# kk_sem_ultrahang_hw.net
KiCad netlist of a schematic drawn in Altium Designer
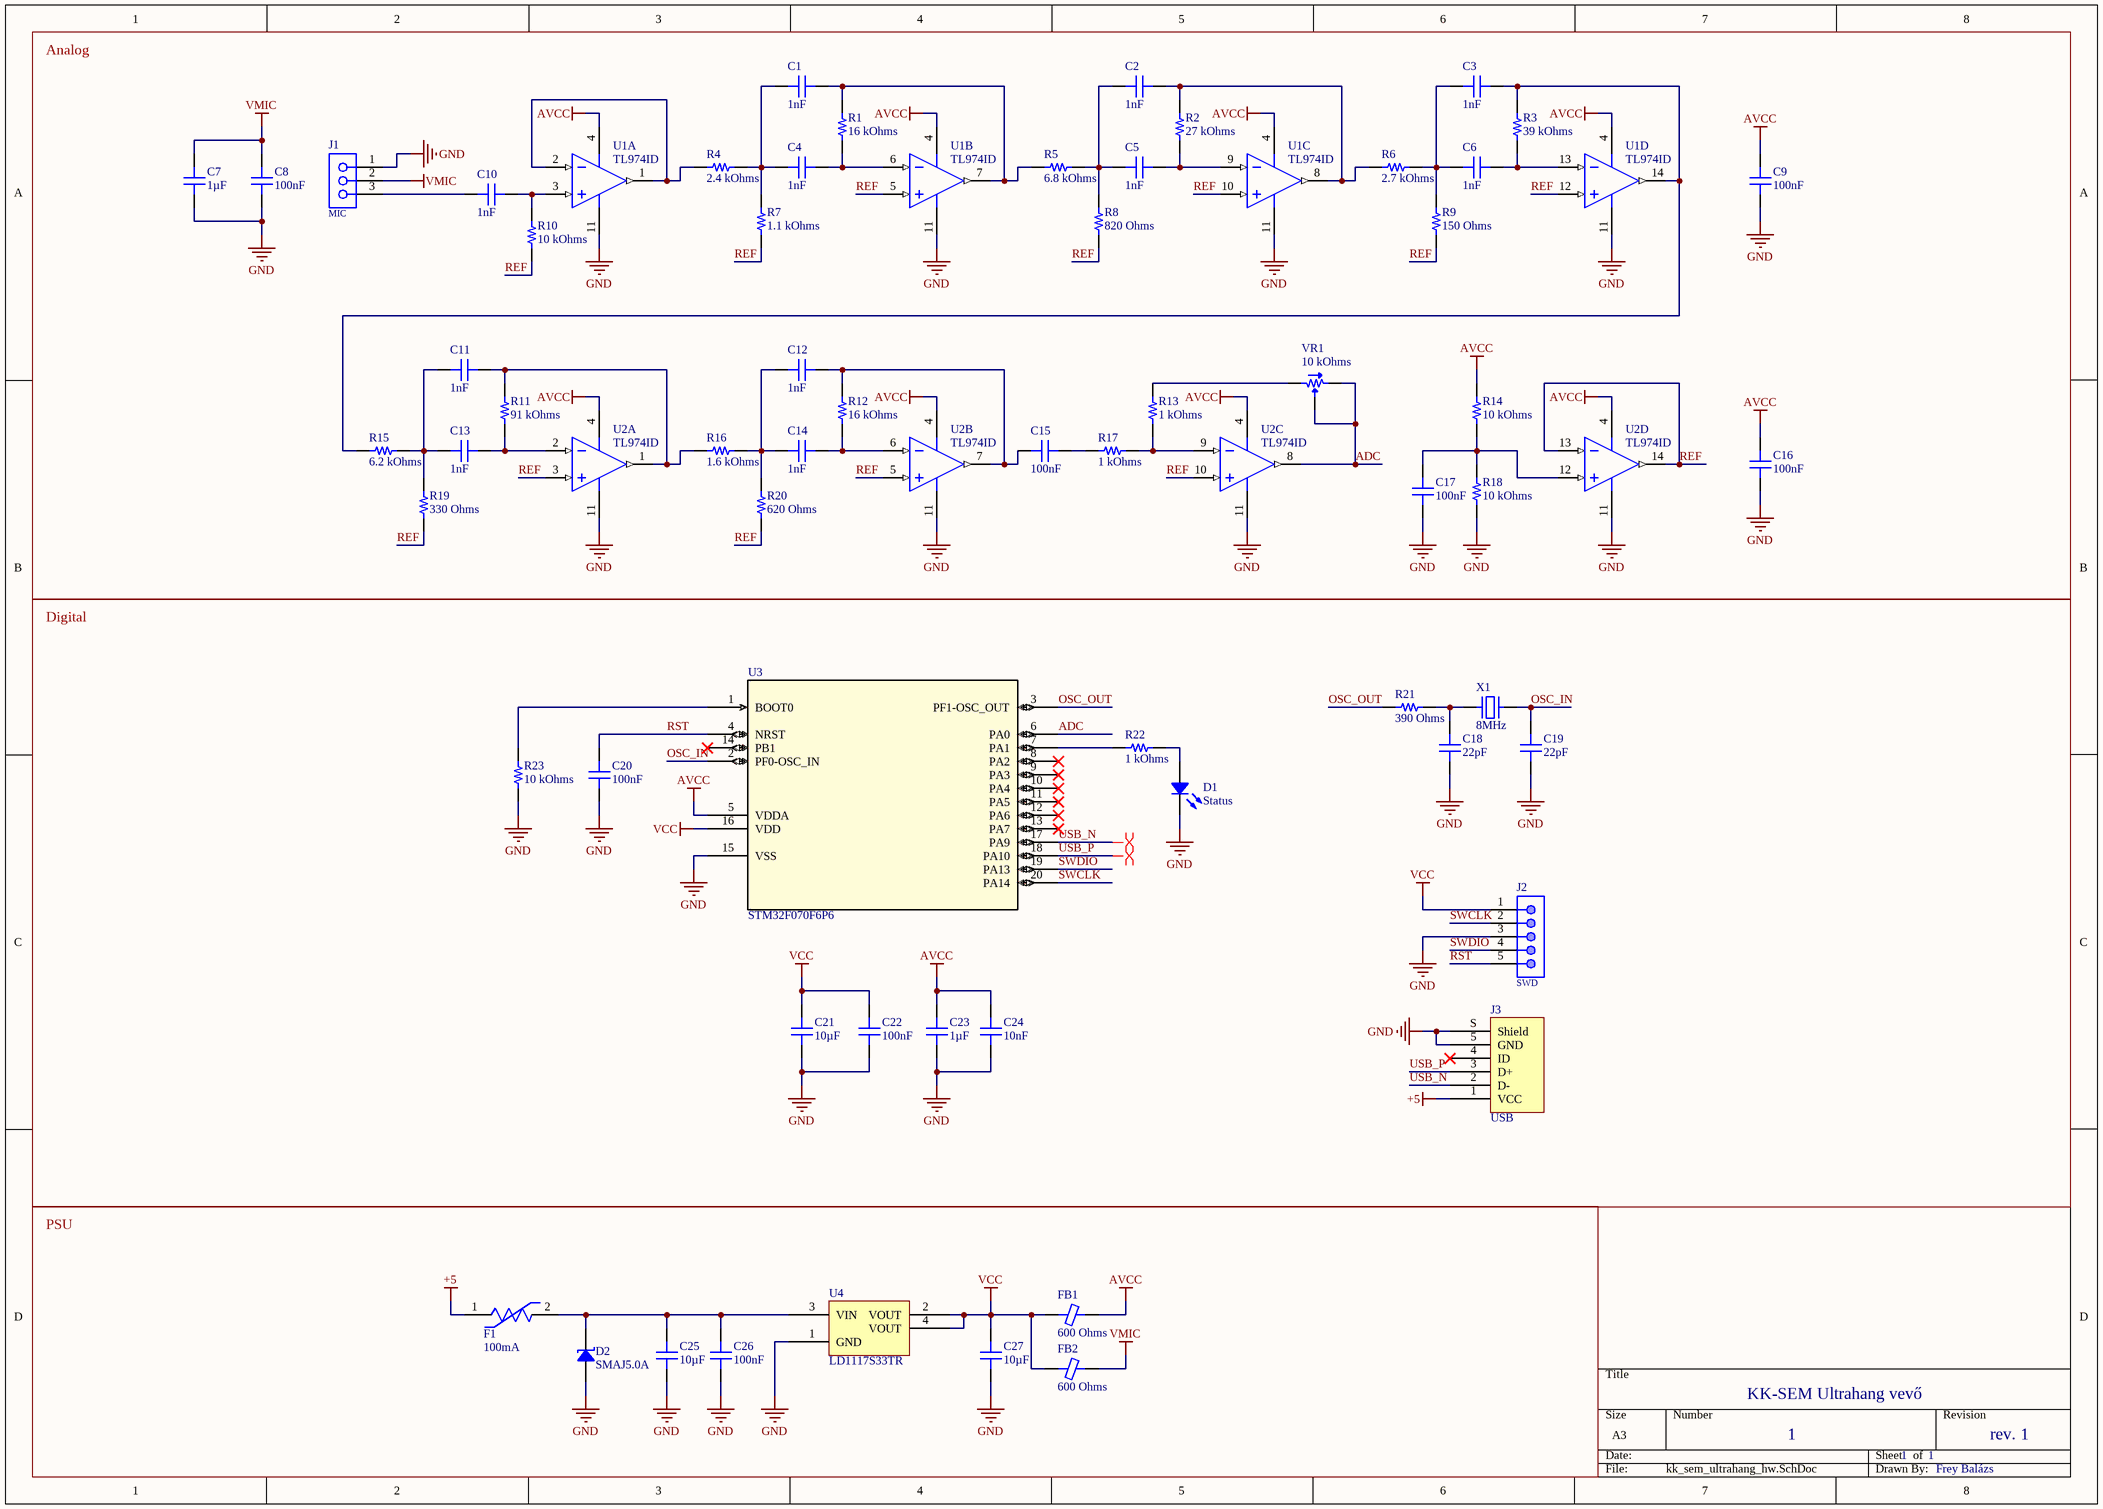
[diagram p0: kk_sem_ultrahang_hw.SchDoc]

(export (version "E")
  (design (tool "Eeschema 10.0.6"))
  (components
    (comp (ref "C1")
      (value "1nF")
      (footprint "CAP 0805_2012")
      (description "CAP CER 1000PF 50V C0G/NP0 0805")
      (fields (field (name "PART NUMBER") "C0805C102K5GACTU") (field (name "MANUFACTURER") "KEMET"))
      (libsource (lib "Celestial Altium Library - altium_library") (part "Capacitor"))
    )
    (comp (ref "C2")
      (value "1nF")
      (footprint "CAP 0805_2012")
      (description "CAP CER 1000PF 50V C0G/NP0 0805")
      (fields (field (name "PART NUMBER") "C0805C102K5GACTU") (field (name "MANUFACTURER") "KEMET"))
      (libsource (lib "Celestial Altium Library - altium_library") (part "Capacitor"))
    )
    (comp (ref "C3")
      (value "1nF")
      (footprint "CAP 0805_2012")
      (description "CAP CER 1000PF 50V C0G/NP0 0805")
      (fields (field (name "PART NUMBER") "C0805C102K5GACTU") (field (name "MANUFACTURER") "KEMET"))
      (libsource (lib "Celestial Altium Library - altium_library") (part "Capacitor"))
    )
    (comp (ref "C4")
      (value "1nF")
      (footprint "CAP 0805_2012")
      (description "CAP CER 1000PF 50V C0G/NP0 0805")
      (fields (field (name "PART NUMBER") "C0805C102K5GACTU") (field (name "MANUFACTURER") "KEMET"))
      (libsource (lib "Celestial Altium Library - altium_library") (part "Capacitor"))
    )
    (comp (ref "C5")
      (value "1nF")
      (footprint "CAP 0805_2012")
      (description "CAP CER 1000PF 50V C0G/NP0 0805")
      (fields (field (name "PART NUMBER") "C0805C102K5GACTU") (field (name "MANUFACTURER") "KEMET"))
      (libsource (lib "Celestial Altium Library - altium_library") (part "Capacitor"))
    )
    (comp (ref "C6")
      (value "1nF")
      (footprint "CAP 0805_2012")
      (description "CAP CER 1000PF 50V C0G/NP0 0805")
      (fields (field (name "PART NUMBER") "C0805C102K5GACTU") (field (name "MANUFACTURER") "KEMET"))
      (libsource (lib "Celestial Altium Library - altium_library") (part "Capacitor"))
    )
    (comp (ref "C7")
      (value "1µF")
      (footprint "CAP 0805_2012")
      (description "CAP CER 1UF 16V X7R 0805")
      (fields (field (name "PART NUMBER") "C0805C105K4RACTU") (field (name "MANUFACTURER") "KEMET"))
      (libsource (lib "Celestial Altium Library - altium_library") (part "Capacitor"))
    )
    (comp (ref "C8")
      (value "100nF")
      (footprint "CAP 0805_2012")
      (description "CAP CER 0.1UF 50V X7R 0805")
      (fields (field (name "PART NUMBER") "CC0805MRX7R9BB104") (field (name "MANUFACTURER") "Yageo"))
      (libsource (lib "Celestial Altium Library - altium_library") (part "Capacitor"))
    )
    (comp (ref "C9")
      (value "100nF")
      (footprint "CAP 0805_2012")
      (description "CAP CER 0.1UF 50V X7R 0805")
      (fields (field (name "PART NUMBER") "CC0805MRX7R9BB104") (field (name "MANUFACTURER") "Yageo"))
      (libsource (lib "Celestial Altium Library - altium_library") (part "Capacitor"))
    )
    (comp (ref "C10")
      (value "1nF")
      (footprint "CAP 0805_2012")
      (description "CAP CER 1000PF 50V C0G/NP0 0805")
      (fields (field (name "PART NUMBER") "C0805C102K5GACTU") (field (name "MANUFACTURER") "KEMET"))
      (libsource (lib "Celestial Altium Library - altium_library") (part "Capacitor"))
    )
    (comp (ref "C11")
      (value "1nF")
      (footprint "CAP 0805_2012")
      (description "CAP CER 1000PF 50V C0G/NP0 0805")
      (fields (field (name "PART NUMBER") "C0805C102K5GACTU") (field (name "MANUFACTURER") "KEMET"))
      (libsource (lib "Celestial Altium Library - altium_library") (part "Capacitor"))
    )
    (comp (ref "C12")
      (value "1nF")
      (footprint "CAP 0805_2012")
      (description "CAP CER 1000PF 50V C0G/NP0 0805")
      (fields (field (name "PART NUMBER") "C0805C102K5GACTU") (field (name "MANUFACTURER") "KEMET"))
      (libsource (lib "Celestial Altium Library - altium_library") (part "Capacitor"))
    )
    (comp (ref "C13")
      (value "1nF")
      (footprint "CAP 0805_2012")
      (description "CAP CER 1000PF 50V C0G/NP0 0805")
      (fields (field (name "PART NUMBER") "C0805C102K5GACTU") (field (name "MANUFACTURER") "KEMET"))
      (libsource (lib "Celestial Altium Library - altium_library") (part "Capacitor"))
    )
    (comp (ref "C14")
      (value "1nF")
      (footprint "CAP 0805_2012")
      (description "CAP CER 1000PF 50V C0G/NP0 0805")
      (fields (field (name "PART NUMBER") "C0805C102K5GACTU") (field (name "MANUFACTURER") "KEMET"))
      (libsource (lib "Celestial Altium Library - altium_library") (part "Capacitor"))
    )
    (comp (ref "C15")
      (value "100nF")
      (footprint "CAP 0805_2012")
      (description "CAP CER 0.1UF 50V X7R 0805")
      (fields (field (name "PART NUMBER") "CC0805MRX7R9BB104") (field (name "MANUFACTURER") "Yageo"))
      (libsource (lib "Celestial Altium Library - altium_library") (part "Capacitor"))
    )
    (comp (ref "C16")
      (value "100nF")
      (footprint "CAP 0805_2012")
      (description "CAP CER 0.1UF 50V X7R 0805")
      (fields (field (name "PART NUMBER") "CC0805MRX7R9BB104") (field (name "MANUFACTURER") "Yageo"))
      (libsource (lib "Celestial Altium Library - altium_library") (part "Capacitor"))
    )
    (comp (ref "C17")
      (value "100nF")
      (footprint "CAP 0805_2012")
      (description "CAP CER 0.1UF 50V X7R 0805")
      (fields (field (name "PART NUMBER") "CC0805MRX7R9BB104") (field (name "MANUFACTURER") "Yageo"))
      (libsource (lib "Celestial Altium Library - altium_library") (part "Capacitor"))
    )
    (comp (ref "C18")
      (value "22pF")
      (footprint "CAP 0805_2012")
      (description "CAP CER 22PF 50V C0G/NP0 0805")
      (fields (field (name "PART NUMBER") "C0805C220J5GACAUTO") (field (name "MANUFACTURER") "KEMET"))
      (libsource (lib "Celestial Altium Library - altium_library") (part "Capacitor"))
    )
    (comp (ref "C19")
      (value "22pF")
      (footprint "CAP 0805_2012")
      (description "CAP CER 22PF 50V C0G/NP0 0805")
      (fields (field (name "PART NUMBER") "C0805C220J5GACAUTO") (field (name "MANUFACTURER") "KEMET"))
      (libsource (lib "Celestial Altium Library - altium_library") (part "Capacitor"))
    )
    (comp (ref "C20")
      (value "100nF")
      (footprint "CAP 0805_2012")
      (description "CAP CER 0.1UF 50V X7R 0805")
      (fields (field (name "PART NUMBER") "CC0805MRX7R9BB104") (field (name "MANUFACTURER") "Yageo"))
      (libsource (lib "Celestial Altium Library - altium_library") (part "Capacitor"))
    )
    (comp (ref "C21")
      (value "10µF")
      (footprint "CAP 0805_2012")
      (description "CAP CER 10UF 16V X5R 0805")
      (fields
        (field (name "PART NUMBER") "CGA4J1X5R1C106K125AC")
        (field (name "MANUFACTURER") "TDK Corporation")
      )
      (libsource (lib "Celestial Altium Library - altium_library") (part "Capacitor"))
    )
    (comp (ref "C22")
      (value "100nF")
      (footprint "CAP 0805_2012")
      (description "CAP CER 0.1UF 50V X7R 0805")
      (fields (field (name "PART NUMBER") "CC0805MRX7R9BB104") (field (name "MANUFACTURER") "Yageo"))
      (libsource (lib "Celestial Altium Library - altium_library") (part "Capacitor"))
    )
    (comp (ref "C23")
      (value "1µF")
      (footprint "CAP 0805_2012")
      (description "CAP CER 1UF 16V X7R 0805")
      (fields (field (name "PART NUMBER") "C0805C105K4RACTU") (field (name "MANUFACTURER") "KEMET"))
      (libsource (lib "Celestial Altium Library - altium_library") (part "Capacitor"))
    )
    (comp (ref "C24")
      (value "10nF")
      (footprint "CAP 0805_2012")
      (description "CAP CER 10000PF 50V X7R 0805")
      (fields (field (name "PART NUMBER") "C0805F103K5RACTU") (field (name "MANUFACTURER") "KEMET"))
      (libsource (lib "Celestial Altium Library - altium_library") (part "Capacitor"))
    )
    (comp (ref "C25")
      (value "10µF")
      (footprint "CAP 0805_2012")
      (description "CAP CER 10UF 16V X5R 0805")
      (fields
        (field (name "PART NUMBER") "CGA4J1X5R1C106K125AC")
        (field (name "MANUFACTURER") "TDK Corporation")
      )
      (libsource (lib "Celestial Altium Library - altium_library") (part "Capacitor"))
    )
    (comp (ref "C26")
      (value "100nF")
      (footprint "CAP 0805_2012")
      (description "CAP CER 0.1UF 50V X7R 0805")
      (fields (field (name "PART NUMBER") "CC0805MRX7R9BB104") (field (name "MANUFACTURER") "Yageo"))
      (libsource (lib "Celestial Altium Library - altium_library") (part "Capacitor"))
    )
    (comp (ref "C27")
      (value "10µF")
      (footprint "CAP 0805_2012")
      (description "CAP CER 10UF 16V X5R 0805")
      (fields
        (field (name "PART NUMBER") "CGA4J1X5R1C106K125AC")
        (field (name "MANUFACTURER") "TDK Corporation")
      )
      (libsource (lib "Celestial Altium Library - altium_library") (part "Capacitor"))
    )
    (comp (ref "D1")
      (value "Status")
      (footprint "LED 0805_2012 GREEN")
      (description "LED GREEN 0805 SMD")
      (fields (field (name "PART NUMBER") "5975316507F") (field (name "MANUFACTURER") "Dialight"))
      (libsource (lib "Celestial Altium Library - altium_library") (part "LED"))
    )
    (comp (ref "D2")
      (value "SMAJ5.0A")
      (footprint "DO214AC SMA")
      (description "TVS DIODE 5V 9.2V DO214AC")
      (fields (field (name "MANUFACTURER") "Littelfuse Inc."))
      (libsource (lib "Celestial Altium Library - altium_library") (part "DIODE TVS UNI"))
    )
    (comp (ref "F1")
      (value "100mA")
      (footprint "Littelfuse_1210L_MFG")
      (description "FUSE PTC RESET FUSE 30V 200MA 1210")
      (fields (field (name "DIGIKEY PART NUMBER") "F3350CT-ND") (field (name "MANUFACTURER") "Littelfuse"))
      (libsource (lib "Fuse_Littelfuse_1210L020WR-1") (part "1210L020WR"))
    )
    (comp (ref "FB1")
      (value "600 Ohms")
      (footprint "FER 0805_2012")
      (description "EMI BEAD FILETER")
      (fields
        (field (name "PART NUMBER") "BBPY00201209601Y00")
        (field (name "MANUFACTURER") "Chilisin Electronics")
      )
      (libsource (lib "Celestial Altium Library - altium_library") (part "Ferrite Chip"))
    )
    (comp (ref "FB2")
      (value "600 Ohms")
      (footprint "FER 0805_2012")
      (description "EMI BEAD FILETER")
      (fields
        (field (name "PART NUMBER") "BBPY00201209601Y00")
        (field (name "MANUFACTURER") "Chilisin Electronics")
      )
      (libsource (lib "Celestial Altium Library - altium_library") (part "Ferrite Chip"))
    )
    (comp (ref "J1")
      (value "MIC")
      (footprint "61300311821")
      (description "WR-PHD Socket Header, THT, pitch 2.54mm, Single Row, Vertical, 3p")
      (fields
        (field (name "MANUFACTURER PART NUMBER") "61300311821")
        (field (name "MANUFACTURER") "Wurth Elektronik")
      )
      (libsource (lib "Altium_WR-PHD (rev20a)") (part "61300311821"))
    )
    (comp (ref "J2")
      (value "SWD")
      (footprint "61300511121")
      (description "WR-PHD Pin Header, THT, pitch 2.54mm, Single Row, Vertical, 5p")
      (fields
        (field (name "MANUFACTURER PART NUMBER") "61300511121")
        (field (name "MANUFACTURER") "Wurth Elektronik")
      )
      (libsource (lib "Altium_WR-PHD (rev20a)") (part "61300511121"))
    )
    (comp (ref "J3")
      (value "USB")
      (footprint "FCI USB 10033526-N3212LF")
      (description "CONN RCPT MINI USB B 5POS SMD RA")
      (fields
        (field (name "PART NUMBER") "10033526-N3212LF")
        (field (name "MANUFACTURER") "Amphenol ICC (FCI)")
      )
      (libsource (lib "Celestial Altium Library - altium_library") (part "USB 2.0 Type B Micro"))
    )
    (comp (ref "R1")
      (value "16 kOhms")
      (footprint "RES 0805_2012")
      (description "RES SMD 16K OHM 1% 1/8W 0805")
      (fields (field (name "PART NUMBER") "CRCW080516K0FKEA") (field (name "MANUFACTURER") "Vishay Dale"))
      (libsource (lib "Celestial Altium Library - altium_library") (part "Resistor"))
    )
    (comp (ref "R2")
      (value "27 kOhms")
      (footprint "RES 0805_2012")
      (description "RES SMD 27K OHM 1% 1/8W 0805")
      (fields
        (field (name "PART NUMBER") "ERJ-6ENF2702V")
        (field (name "MANUFACTURER") "Panasonic Electronic Components")
      )
      (libsource (lib "Celestial Altium Library - altium_library") (part "Resistor"))
    )
    (comp (ref "R3")
      (value "39 kOhms")
      (footprint "RES 0805_2012")
      (description "RES SMD 39K OHM 1% 1/8W 0805")
      (fields (field (name "PART NUMBER") "AC0805FR-0739KL") (field (name "MANUFACTURER") "Yageo"))
      (libsource (lib "Celestial Altium Library - altium_library") (part "Resistor"))
    )
    (comp (ref "R4")
      (value "2.4 kOhms")
      (footprint "RES 0805_2012")
      (description "RES SMD 2.4K OHM 1% 1/8W 0805")
      (fields (field (name "PART NUMBER") "KTR10EZPF2401") (field (name "MANUFACTURER") "Rohm Semiconductor"))
      (libsource (lib "Celestial Altium Library - altium_library") (part "Resistor"))
    )
    (comp (ref "R5")
      (value "6.8 kOhms")
      (footprint "RES 0805_2012")
      (description "RES SMD 6.8K OHM 1% 1/8W 0805")
      (fields
        (field (name "PART NUMBER") "ERJ-6ENF6801V")
        (field (name "MANUFACTURER") "Panasonic Electronic Components")
      )
      (libsource (lib "Celestial Altium Library - altium_library") (part "Resistor"))
    )
    (comp (ref "R6")
      (value "2.7 kOhms")
      (footprint "RES 0805_2012")
      (description "RES SMD 2.7K OHM 1% 1/8W 0805")
      (fields (field (name "PART NUMBER") "CR0805-FX-2701ELF") (field (name "MANUFACTURER") "Bourns Inc."))
      (libsource (lib "Celestial Altium Library - altium_library") (part "Resistor"))
    )
    (comp (ref "R7")
      (value "1.1 kOhms")
      (footprint "RES 0805_2012")
      (description "RES 1.1K OHM 1% 1/8W 0805")
      (fields
        (field (name "PART NUMBER") "RMCF0805FG1K10")
        (field (name "MANUFACTURER") "Stackpole Electronics Inc")
      )
      (libsource (lib "Celestial Altium Library - altium_library") (part "Resistor"))
    )
    (comp (ref "R8")
      (value "820 Ohms")
      (footprint "RES 0805_2012")
      (description "RES 820 OHM 1% 1/8W 0805")
      (fields
        (field (name "PART NUMBER") "RMCF0805FT820R")
        (field (name "MANUFACTURER") "Stackpole Electronics Inc")
      )
      (libsource (lib "Celestial Altium Library - altium_library") (part "Resistor"))
    )
    (comp (ref "R9")
      (value "150 Ohms")
      (footprint "RES 0805_2012")
      (description "RES 150 OHM 1% 1/8W 0805")
      (fields
        (field (name "PART NUMBER") "RMCF0805FT150R")
        (field (name "MANUFACTURER") "Stackpole Electronics Inc")
      )
      (libsource (lib "Celestial Altium Library - altium_library") (part "Resistor"))
    )
    (comp (ref "R10")
      (value "10 kOhms")
      (footprint "RES 0805_2012")
      (description "CRGCQ 0805 10K 1%")
      (fields
        (field (name "PART NUMBER") "CRGCQ0805F10K")
        (field (name "MANUFACTURER") "TE Connectivity Passive Product")
      )
      (libsource (lib "Celestial Altium Library - altium_library") (part "Resistor"))
    )
    (comp (ref "R11")
      (value "91 kOhms")
      (footprint "RES 0805_2012")
      (description "RES SMD 91K OHM 1% 1/8W 0805")
      (fields (field (name "PART NUMBER") "CRCW080591K0FKEA") (field (name "MANUFACTURER") "Vishay Dale"))
      (libsource (lib "Celestial Altium Library - altium_library") (part "Resistor"))
    )
    (comp (ref "R12")
      (value "16 kOhms")
      (footprint "RES 0805_2012")
      (description "RES SMD 16K OHM 1% 1/8W 0805")
      (fields (field (name "PART NUMBER") "CRCW080516K0FKEA") (field (name "MANUFACTURER") "Vishay Dale"))
      (libsource (lib "Celestial Altium Library - altium_library") (part "Resistor"))
    )
    (comp (ref "R13")
      (value "1 kOhms")
      (footprint "RES 0805_2012")
      (description "RES SMD 1K OHM 1% 1/8W 0805")
      (fields (field (name "PART NUMBER") "CRCW08051K00FKEA") (field (name "MANUFACTURER") "Vishay Dale"))
      (libsource (lib "Celestial Altium Library - altium_library") (part "Resistor"))
    )
    (comp (ref "R14")
      (value "10 kOhms")
      (footprint "RES 0805_2012")
      (description "CRGCQ 0805 10K 1%")
      (fields
        (field (name "PART NUMBER") "CRGCQ0805F10K")
        (field (name "MANUFACTURER") "TE Connectivity Passive Product")
      )
      (libsource (lib "Celestial Altium Library - altium_library") (part "Resistor"))
    )
    (comp (ref "R15")
      (value "6.2 kOhms")
      (footprint "RES 0805_2012")
      (description "RES 6.2K OHM 1% 1/8W 0805")
      (fields
        (field (name "PART NUMBER") "RMCF0805FT6K20")
        (field (name "MANUFACTURER") "Stackpole Electronics Inc")
      )
      (libsource (lib "Celestial Altium Library - altium_library") (part "Resistor"))
    )
    (comp (ref "R16")
      (value "1.6 kOhms")
      (footprint "RES 0805_2012")
      (description "RES SMD 1.6K OHM 1% 1/8W 0805")
      (fields (field (name "PART NUMBER") "AC0805FR-071K6L") (field (name "MANUFACTURER") "Yageo"))
      (libsource (lib "Celestial Altium Library - altium_library") (part "Resistor"))
    )
    (comp (ref "R17")
      (value "1 kOhms")
      (footprint "RES 0805_2012")
      (description "RES SMD 1K OHM 1% 1/8W 0805")
      (fields (field (name "PART NUMBER") "CRCW08051K00FKEA") (field (name "MANUFACTURER") "Vishay Dale"))
      (libsource (lib "Celestial Altium Library - altium_library") (part "Resistor"))
    )
    (comp (ref "R18")
      (value "10 kOhms")
      (footprint "RES 0805_2012")
      (description "CRGCQ 0805 10K 1%")
      (fields
        (field (name "PART NUMBER") "CRGCQ0805F10K")
        (field (name "MANUFACTURER") "TE Connectivity Passive Product")
      )
      (libsource (lib "Celestial Altium Library - altium_library") (part "Resistor"))
    )
    (comp (ref "R19")
      (value "330 Ohms")
      (footprint "RES 0805_2012")
      (description "RES SMD 330 OHM 1% 1/8W 0805")
      (fields (field (name "PART NUMBER") "RC0805FR-07330RL") (field (name "MANUFACTURER") "Yageo"))
      (libsource (lib "Celestial Altium Library - altium_library") (part "Resistor"))
    )
    (comp (ref "R20")
      (value "620 Ohms")
      (footprint "RES 0805_2012")
      (description "RES SMD 620 OHM 1% 1/8W 0805")
      (fields (field (name "PART NUMBER") "KTR10EZPF6200") (field (name "MANUFACTURER") "Rohm Semiconductor"))
      (libsource (lib "Celestial Altium Library - altium_library") (part "Resistor"))
    )
    (comp (ref "R21")
      (value "390 Ohms")
      (footprint "RES 0805_2012")
      (description "RES 390 OHM 5% 1/8W 0805")
      (fields
        (field (name "PART NUMBER") "RMCF0805JT390R")
        (field (name "MANUFACTURER") "Stackpole Electronics Inc")
      )
      (libsource (lib "Celestial Altium Library - altium_library") (part "Resistor"))
    )
    (comp (ref "R22")
      (value "1 kOhms")
      (footprint "RES 0805_2012")
      (description "RES SMD 1K OHM 1% 1/8W 0805")
      (fields (field (name "PART NUMBER") "CRCW08051K00FKEA") (field (name "MANUFACTURER") "Vishay Dale"))
      (libsource (lib "Celestial Altium Library - altium_library") (part "Resistor"))
    )
    (comp (ref "R23")
      (value "10 kOhms")
      (footprint "RES 0805_2012")
      (description "CRGCQ 0805 10K 1%")
      (fields
        (field (name "PART NUMBER") "CRGCQ0805F10K")
        (field (name "MANUFACTURER") "TE Connectivity Passive Product")
      )
      (libsource (lib "Celestial Altium Library - altium_library") (part "Resistor"))
    )
    (comp (ref "U1")
      (value "TL974ID")
      (footprint "TI-D14_N")
      (fields (field (name "MANUFACTURER") "Texas Instruments"))
      (libsource (lib "TI Amplifiers and Linear Operational Amplifier General Purpose") (part "TL974ID"))
    )
    (comp (ref "U2")
      (value "TL974ID")
      (footprint "TI-D14_N")
      (fields (field (name "MANUFACTURER") "Texas Instruments"))
      (libsource (lib "TI Amplifiers and Linear Operational Amplifier General Purpose") (part "TL974ID"))
    )
    (comp (ref "U3")
      (value "STM32F070F6P6")
      (footprint "TSSOP20")
      (description "No Description Available")
      (fields (field (name "COPYRIGHT") "Copyright (C) 2018 Accelerated Designs. All rights reserved"))
      (libsource (lib "STM32F070F6") (part "STM32F070F6P6"))
    )
    (comp (ref "U4")
      (value "LD1117S33TR")
      (footprint "ST SOT-223")
      (description "IC REG LINEAR 3.3V 800MA SOT223")
      (fields (field (name "MANUFACTURER") "STMicroelectronics"))
      (libsource (lib "Celestial Altium Library - altium_library") (part "ST LD1117"))
    )
    (comp (ref "VR1")
      (value "10 kOhms")
      (footprint "Bourns 3314G-1")
      (description "Bourns 3314G-1")
      (libsource (lib "CustomComponents") (part "Bourns 3314G-1"))
    )
    (comp (ref "X1")
      (value "8MHz")
      (footprint "ABRACON ABLS")
      (description "CRYSTAL 8.000MHZ 18PF SMD")
      (fields (field (name "PART NUMBER") "ABLS-8.000MHZ-SD7Y-T") (field (name "MANUFACTURER") "Abracon LLC"))
      (libsource (lib "Celestial Altium Library - altium_library") (part "Abracon Crystal ABLS"))
    )
  )
  (nets
    (net (code "1") (name "+5") (class "Default")
      (node (ref "F1") (pin "1") (pinfunction "1_1") (pintype "passive"))
      (node (ref "J3") (pin "1") (pinfunction "VCC_1") (pintype "passive"))
    )
    (net (code "2") (name "/ADC") (class "Default")
      (node (ref "U2") (pin "8") (pinfunction "OUT3_8") (pintype "output"))
      (node (ref "U3") (pin "6") (pinfunction "PA0_6") (pintype "bidirectional"))
      (node (ref "VR1") (pin "2") (pinfunction "2_2") (pintype "passive"))
      (node (ref "VR1") (pin "3") (pinfunction "3_3") (pintype "passive"))
    )
    (net (code "3") (name "/OSC_IN") (class "Default")
      (node (ref "C19") (pin "2") (pinfunction "2_2") (pintype "passive"))
      (node (ref "U3") (pin "2") (pinfunction "PF0-OSC_IN_2") (pintype "bidirectional"))
      (node (ref "X1") (pin "2") (pinfunction "2_2") (pintype "passive"))
    )
    (net (code "4") (name "/OSC_OUT") (class "Default")
      (node (ref "R21") (pin "1") (pinfunction "1_1") (pintype "passive"))
      (node (ref "U3") (pin "3") (pinfunction "PF1-OSC_OUT_3") (pintype "bidirectional"))
    )
    (net (code "5") (name "/REF") (class "Default")
      (node (ref "R10") (pin "1") (pinfunction "1_1") (pintype "passive"))
      (node (ref "R19") (pin "1") (pinfunction "1_1") (pintype "passive"))
      (node (ref "R20") (pin "1") (pinfunction "1_1") (pintype "passive"))
      (node (ref "R7") (pin "1") (pinfunction "1_1") (pintype "passive"))
      (node (ref "R8") (pin "1") (pinfunction "1_1") (pintype "passive"))
      (node (ref "R9") (pin "1") (pinfunction "1_1") (pintype "passive"))
      (node (ref "U1") (pin "10") (pinfunction "IN3+_10") (pintype "input"))
      (node (ref "U1") (pin "12") (pinfunction "IN4+_12") (pintype "input"))
      (node (ref "U1") (pin "5") (pinfunction "IN2+_5") (pintype "input"))
      (node (ref "U2") (pin "10") (pinfunction "IN3+_10") (pintype "input"))
      (node (ref "U2") (pin "13") (pinfunction "IN4-_13") (pintype "input"))
      (node (ref "U2") (pin "14") (pinfunction "OUT4_14") (pintype "output"))
      (node (ref "U2") (pin "3") (pinfunction "IN1+_3") (pintype "input"))
      (node (ref "U2") (pin "5") (pinfunction "IN2+_5") (pintype "input"))
    )
    (net (code "6") (name "/RST") (class "Default")
      (node (ref "C20") (pin "2") (pinfunction "2_2") (pintype "passive"))
      (node (ref "J2") (pin "5") (pinfunction "5_5") (pintype "passive"))
      (node (ref "U3") (pin "4") (pinfunction "NRST_4") (pintype "bidirectional"))
    )
    (net (code "7") (name "/SWCLK") (class "Default")
      (node (ref "J2") (pin "2") (pinfunction "2_2") (pintype "passive"))
      (node (ref "U3") (pin "20") (pinfunction "PA14_20") (pintype "bidirectional"))
    )
    (net (code "8") (name "/SWDIO") (class "Default")
      (node (ref "J2") (pin "4") (pinfunction "4_4") (pintype "passive"))
      (node (ref "U3") (pin "19") (pinfunction "PA13_19") (pintype "bidirectional"))
    )
    (net (code "9") (name "/USB_N") (class "Default")
      (node (ref "J3") (pin "2") (pinfunction "D-_2") (pintype "passive"))
      (node (ref "U3") (pin "17") (pinfunction "PA9_17") (pintype "bidirectional"))
    )
    (net (code "10") (name "/USB_P") (class "Default")
      (node (ref "J3") (pin "3") (pinfunction "D+_3") (pintype "passive"))
      (node (ref "U3") (pin "18") (pinfunction "PA10_18") (pintype "bidirectional"))
    )
    (net (code "11") (name "AVCC") (class "Default")
      (node (ref "C16") (pin "2") (pinfunction "2_2") (pintype "passive"))
      (node (ref "C23") (pin "2") (pinfunction "2_2") (pintype "passive"))
      (node (ref "C24") (pin "2") (pinfunction "2_2") (pintype "passive"))
      (node (ref "C9") (pin "2") (pinfunction "2_2") (pintype "passive"))
      (node (ref "FB1") (pin "2") (pinfunction "2_2") (pintype "passive"))
      (node (ref "R14") (pin "2") (pinfunction "2_2") (pintype "passive"))
      (node (ref "U1") (pin "4") (pinfunction "VCC+_4") (pintype "power_in"))
      (node (ref "U2") (pin "4") (pinfunction "VCC+_4") (pintype "power_in"))
      (node (ref "U3") (pin "5") (pinfunction "VDDA_5") (pintype "power_in"))
    )
    (net (code "12") (name "GND") (class "Default")
      (node (ref "C16") (pin "1") (pinfunction "1_1") (pintype "passive"))
      (node (ref "C17") (pin "1") (pinfunction "1_1") (pintype "passive"))
      (node (ref "C18") (pin "1") (pinfunction "1_1") (pintype "passive"))
      (node (ref "C19") (pin "1") (pinfunction "1_1") (pintype "passive"))
      (node (ref "C20") (pin "1") (pinfunction "1_1") (pintype "passive"))
      (node (ref "C21") (pin "1") (pinfunction "1_1") (pintype "passive"))
      (node (ref "C22") (pin "1") (pinfunction "1_1") (pintype "passive"))
      (node (ref "C23") (pin "1") (pinfunction "1_1") (pintype "passive"))
      (node (ref "C24") (pin "1") (pinfunction "1_1") (pintype "passive"))
      (node (ref "C25") (pin "1") (pinfunction "1_1") (pintype "passive"))
      (node (ref "C26") (pin "1") (pinfunction "1_1") (pintype "passive"))
      (node (ref "C27") (pin "1") (pinfunction "1_1") (pintype "passive"))
      (node (ref "C7") (pin "1") (pinfunction "1_1") (pintype "passive"))
      (node (ref "C8") (pin "1") (pinfunction "1_1") (pintype "passive"))
      (node (ref "C9") (pin "1") (pinfunction "1_1") (pintype "passive"))
      (node (ref "D1") (pin "2") (pinfunction "2_2") (pintype "passive"))
      (node (ref "D2") (pin "1") (pinfunction "1_1") (pintype "passive"))
      (node (ref "J1") (pin "1") (pinfunction "1_1") (pintype "passive"))
      (node (ref "J2") (pin "3") (pinfunction "3_3") (pintype "passive"))
      (node (ref "J3") (pin "5") (pinfunction "GND_5") (pintype "passive"))
      (node (ref "J3") (pin "S") (pinfunction "Shield_S") (pintype "passive"))
      (node (ref "R18") (pin "1") (pinfunction "1_1") (pintype "passive"))
      (node (ref "R23") (pin "1") (pinfunction "1_1") (pintype "passive"))
      (node (ref "U1") (pin "11") (pinfunction "VCC-_11") (pintype "power_in"))
      (node (ref "U2") (pin "11") (pinfunction "VCC-_11") (pintype "power_in"))
      (node (ref "U3") (pin "15") (pinfunction "VSS_15") (pintype "power_in"))
      (node (ref "U4") (pin "1") (pinfunction "GND_1") (pintype "passive"))
    )
    (net (code "13") (name "Net-(C1-Pad1)") (class "Default")
      (node (ref "C1") (pin "1") (pinfunction "1_1") (pintype "passive"))
      (node (ref "C4") (pin "1") (pinfunction "1_1") (pintype "passive"))
      (node (ref "R4") (pin "2") (pinfunction "2_2") (pintype "passive"))
      (node (ref "R7") (pin "2") (pinfunction "2_2") (pintype "passive"))
    )
    (net (code "14") (name "Net-(C2-Pad1)") (class "Default")
      (node (ref "C2") (pin "1") (pinfunction "1_1") (pintype "passive"))
      (node (ref "C5") (pin "1") (pinfunction "1_1") (pintype "passive"))
      (node (ref "R5") (pin "2") (pinfunction "2_2") (pintype "passive"))
      (node (ref "R8") (pin "2") (pinfunction "2_2") (pintype "passive"))
    )
    (net (code "15") (name "Net-(C3-Pad1)") (class "Default")
      (node (ref "C3") (pin "1") (pinfunction "1_1") (pintype "passive"))
      (node (ref "C6") (pin "1") (pinfunction "1_1") (pintype "passive"))
      (node (ref "R6") (pin "2") (pinfunction "2_2") (pintype "passive"))
      (node (ref "R9") (pin "2") (pinfunction "2_2") (pintype "passive"))
    )
    (net (code "16") (name "Net-(C10-Pad1)") (class "Default")
      (node (ref "C10") (pin "1") (pinfunction "1_1") (pintype "passive"))
      (node (ref "J1") (pin "3") (pinfunction "3_3") (pintype "passive"))
    )
    (net (code "17") (name "Net-(C11-Pad1)") (class "Default")
      (node (ref "C11") (pin "1") (pinfunction "1_1") (pintype "passive"))
      (node (ref "C13") (pin "1") (pinfunction "1_1") (pintype "passive"))
      (node (ref "R15") (pin "2") (pinfunction "2_2") (pintype "passive"))
      (node (ref "R19") (pin "2") (pinfunction "2_2") (pintype "passive"))
    )
    (net (code "18") (name "Net-(C12-Pad1)") (class "Default")
      (node (ref "C12") (pin "1") (pinfunction "1_1") (pintype "passive"))
      (node (ref "C14") (pin "1") (pinfunction "1_1") (pintype "passive"))
      (node (ref "R16") (pin "2") (pinfunction "2_2") (pintype "passive"))
      (node (ref "R20") (pin "2") (pinfunction "2_2") (pintype "passive"))
    )
    (net (code "19") (name "Net-(C15-Pad1)") (class "Default")
      (node (ref "C15") (pin "1") (pinfunction "1_1") (pintype "passive"))
      (node (ref "R17") (pin "1") (pinfunction "1_1") (pintype "passive"))
    )
    (net (code "20") (name "Net-(C18-Pad2)") (class "Default")
      (node (ref "C18") (pin "2") (pinfunction "2_2") (pintype "passive"))
      (node (ref "R21") (pin "2") (pinfunction "2_2") (pintype "passive"))
      (node (ref "X1") (pin "1") (pinfunction "1_1") (pintype "passive"))
    )
    (net (code "21") (name "Net-(D1-Pad1)") (class "Default")
      (node (ref "D1") (pin "1") (pinfunction "1_1") (pintype "passive"))
      (node (ref "R22") (pin "2") (pinfunction "2_2") (pintype "passive"))
    )
    (net (code "22") (name "Net-(R13-Pad2)") (class "Default")
      (node (ref "R13") (pin "2") (pinfunction "2_2") (pintype "passive"))
      (node (ref "VR1") (pin "1") (pinfunction "1_1") (pintype "passive"))
    )
    (net (code "23") (name "Net-(U1A-IN1+)") (class "Default")
      (node (ref "C10") (pin "2") (pinfunction "2_2") (pintype "passive"))
      (node (ref "R10") (pin "2") (pinfunction "2_2") (pintype "passive"))
      (node (ref "U1") (pin "3") (pinfunction "IN1+_3") (pintype "input"))
    )
    (net (code "24") (name "Net-(U1A-IN1-)") (class "Default")
      (node (ref "R4") (pin "1") (pinfunction "1_1") (pintype "passive"))
      (node (ref "U1") (pin "1") (pinfunction "OUT1_1") (pintype "output"))
      (node (ref "U1") (pin "2") (pinfunction "IN1-_2") (pintype "input"))
    )
    (net (code "25") (name "Net-(U1B-IN2-)") (class "Default")
      (node (ref "C4") (pin "2") (pinfunction "2_2") (pintype "passive"))
      (node (ref "R1") (pin "1") (pinfunction "1_1") (pintype "passive"))
      (node (ref "U1") (pin "6") (pinfunction "IN2-_6") (pintype "input"))
    )
    (net (code "26") (name "Net-(U1B-OUT2)") (class "Default")
      (node (ref "C1") (pin "2") (pinfunction "2_2") (pintype "passive"))
      (node (ref "R1") (pin "2") (pinfunction "2_2") (pintype "passive"))
      (node (ref "R5") (pin "1") (pinfunction "1_1") (pintype "passive"))
      (node (ref "U1") (pin "7") (pinfunction "OUT2_7") (pintype "output"))
    )
    (net (code "27") (name "Net-(U1C-IN3-)") (class "Default")
      (node (ref "C5") (pin "2") (pinfunction "2_2") (pintype "passive"))
      (node (ref "R2") (pin "1") (pinfunction "1_1") (pintype "passive"))
      (node (ref "U1") (pin "9") (pinfunction "IN3-_9") (pintype "input"))
    )
    (net (code "28") (name "Net-(U1C-OUT3)") (class "Default")
      (node (ref "C2") (pin "2") (pinfunction "2_2") (pintype "passive"))
      (node (ref "R2") (pin "2") (pinfunction "2_2") (pintype "passive"))
      (node (ref "R6") (pin "1") (pinfunction "1_1") (pintype "passive"))
      (node (ref "U1") (pin "8") (pinfunction "OUT3_8") (pintype "output"))
    )
    (net (code "29") (name "Net-(U1D-IN4-)") (class "Default")
      (node (ref "C6") (pin "2") (pinfunction "2_2") (pintype "passive"))
      (node (ref "R3") (pin "1") (pinfunction "1_1") (pintype "passive"))
      (node (ref "U1") (pin "13") (pinfunction "IN4-_13") (pintype "input"))
    )
    (net (code "30") (name "Net-(U1D-OUT4)") (class "Default")
      (node (ref "C3") (pin "2") (pinfunction "2_2") (pintype "passive"))
      (node (ref "R15") (pin "1") (pinfunction "1_1") (pintype "passive"))
      (node (ref "R3") (pin "2") (pinfunction "2_2") (pintype "passive"))
      (node (ref "U1") (pin "14") (pinfunction "OUT4_14") (pintype "output"))
    )
    (net (code "31") (name "Net-(U2A-IN1-)") (class "Default")
      (node (ref "C13") (pin "2") (pinfunction "2_2") (pintype "passive"))
      (node (ref "R11") (pin "1") (pinfunction "1_1") (pintype "passive"))
      (node (ref "U2") (pin "2") (pinfunction "IN1-_2") (pintype "input"))
    )
    (net (code "32") (name "Net-(U2A-OUT1)") (class "Default")
      (node (ref "C11") (pin "2") (pinfunction "2_2") (pintype "passive"))
      (node (ref "R11") (pin "2") (pinfunction "2_2") (pintype "passive"))
      (node (ref "R16") (pin "1") (pinfunction "1_1") (pintype "passive"))
      (node (ref "U2") (pin "1") (pinfunction "OUT1_1") (pintype "output"))
    )
    (net (code "33") (name "Net-(U2B-IN2-)") (class "Default")
      (node (ref "C14") (pin "2") (pinfunction "2_2") (pintype "passive"))
      (node (ref "R12") (pin "1") (pinfunction "1_1") (pintype "passive"))
      (node (ref "U2") (pin "6") (pinfunction "IN2-_6") (pintype "input"))
    )
    (net (code "34") (name "Net-(U2B-OUT2)") (class "Default")
      (node (ref "C12") (pin "2") (pinfunction "2_2") (pintype "passive"))
      (node (ref "C15") (pin "2") (pinfunction "2_2") (pintype "passive"))
      (node (ref "R12") (pin "2") (pinfunction "2_2") (pintype "passive"))
      (node (ref "U2") (pin "7") (pinfunction "OUT2_7") (pintype "output"))
    )
    (net (code "35") (name "Net-(U2C-IN3-)") (class "Default")
      (node (ref "R13") (pin "1") (pinfunction "1_1") (pintype "passive"))
      (node (ref "R17") (pin "2") (pinfunction "2_2") (pintype "passive"))
      (node (ref "U2") (pin "9") (pinfunction "IN3-_9") (pintype "input"))
    )
    (net (code "36") (name "Net-(U2D-IN4+)") (class "Default")
      (node (ref "C17") (pin "2") (pinfunction "2_2") (pintype "passive"))
      (node (ref "R14") (pin "1") (pinfunction "1_1") (pintype "passive"))
      (node (ref "R18") (pin "2") (pinfunction "2_2") (pintype "passive"))
      (node (ref "U2") (pin "12") (pinfunction "IN4+_12") (pintype "input"))
    )
    (net (code "37") (name "Net-(U3-BOOT0)") (class "Default")
      (node (ref "R23") (pin "2") (pinfunction "2_2") (pintype "passive"))
      (node (ref "U3") (pin "1") (pinfunction "BOOT0_1") (pintype "input"))
    )
    (net (code "38") (name "Net-(U3-PA1)") (class "Default")
      (node (ref "R22") (pin "1") (pinfunction "1_1") (pintype "passive"))
      (node (ref "U3") (pin "7") (pinfunction "PA1_7") (pintype "bidirectional"))
    )
    (net (code "39") (name "Net-(U4-VIN)") (class "Default")
      (node (ref "C25") (pin "2") (pinfunction "2_2") (pintype "passive"))
      (node (ref "C26") (pin "2") (pinfunction "2_2") (pintype "passive"))
      (node (ref "D2") (pin "2") (pinfunction "2_2") (pintype "passive"))
      (node (ref "F1") (pin "2") (pinfunction "2_2") (pintype "passive"))
      (node (ref "U4") (pin "3") (pinfunction "VIN_3") (pintype "passive"))
    )
    (net (code "40") (name "VCC") (class "Default")
      (node (ref "C21") (pin "2") (pinfunction "2_2") (pintype "passive"))
      (node (ref "C22") (pin "2") (pinfunction "2_2") (pintype "passive"))
      (node (ref "C27") (pin "2") (pinfunction "2_2") (pintype "passive"))
      (node (ref "FB1") (pin "1") (pinfunction "1_1") (pintype "passive"))
      (node (ref "FB2") (pin "1") (pinfunction "1_1") (pintype "passive"))
      (node (ref "J2") (pin "1") (pinfunction "1_1") (pintype "passive"))
      (node (ref "U3") (pin "16") (pinfunction "VDD_16") (pintype "power_in"))
      (node (ref "U4") (pin "2") (pinfunction "VOUT_2") (pintype "passive"))
      (node (ref "U4") (pin "4") (pinfunction "VOUT_4") (pintype "passive"))
    )
    (net (code "41") (name "VMIC") (class "Default")
      (node (ref "C7") (pin "2") (pinfunction "2_2") (pintype "passive"))
      (node (ref "C8") (pin "2") (pinfunction "2_2") (pintype "passive"))
      (node (ref "FB2") (pin "2") (pinfunction "2_2") (pintype "passive"))
      (node (ref "J1") (pin "2") (pinfunction "2_2") (pintype "passive"))
    )
    (net (code "42") (name "unconnected-(J3-ID-Pad4)") (class "Default")
      (node (ref "J3") (pin "4") (pinfunction "ID_4") (pintype "passive+no_connect"))
    )
    (net (code "43") (name "unconnected-(U3-PA2-Pad8)") (class "Default")
      (node (ref "U3") (pin "8") (pinfunction "PA2_8") (pintype "bidirectional+no_connect"))
    )
    (net (code "44") (name "unconnected-(U3-PA3-Pad9)") (class "Default")
      (node (ref "U3") (pin "9") (pinfunction "PA3_9") (pintype "bidirectional+no_connect"))
    )
    (net (code "45") (name "unconnected-(U3-PA4-Pad10)") (class "Default")
      (node (ref "U3") (pin "10") (pinfunction "PA4_10") (pintype "bidirectional+no_connect"))
    )
    (net (code "46") (name "unconnected-(U3-PA5-Pad11)") (class "Default")
      (node (ref "U3") (pin "11") (pinfunction "PA5_11") (pintype "bidirectional+no_connect"))
    )
    (net (code "47") (name "unconnected-(U3-PA6-Pad12)") (class "Default")
      (node (ref "U3") (pin "12") (pinfunction "PA6_12") (pintype "bidirectional+no_connect"))
    )
    (net (code "48") (name "unconnected-(U3-PA7-Pad13)") (class "Default")
      (node (ref "U3") (pin "13") (pinfunction "PA7_13") (pintype "bidirectional+no_connect"))
    )
    (net (code "49") (name "unconnected-(U3-PB1-Pad14)") (class "Default")
      (node (ref "U3") (pin "14") (pinfunction "PB1_14") (pintype "bidirectional+no_connect"))
    )
  )
)
